# Controllers.net
KiCad netlist of a schematic drawn in Altium Designer
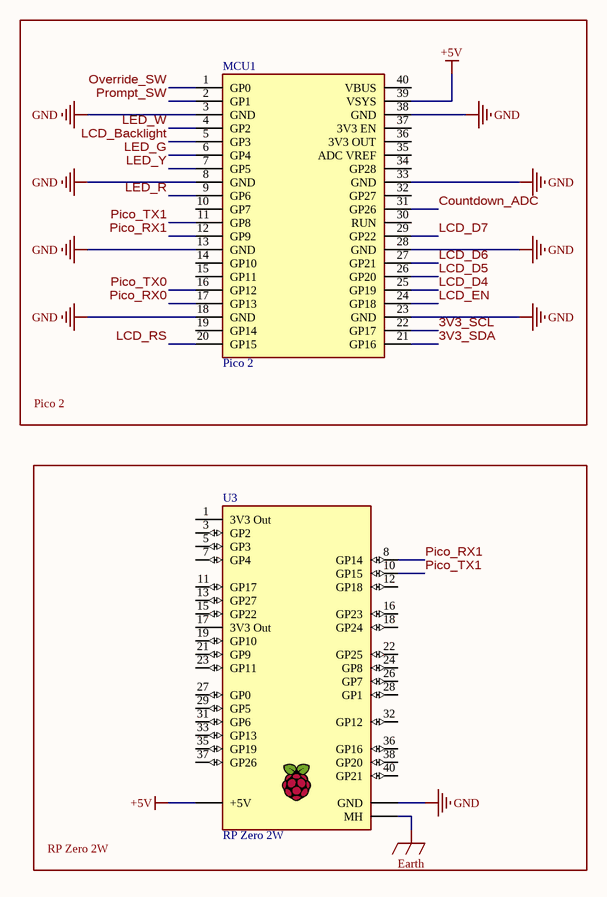
[diagram p0: Controllers.SchDoc]

(export (version "E")
  (design (tool "Eeschema 10.0.6"))
  (components
    (comp (ref "MCU1")
      (value "Pico 2")
      (footprint "[Pi] Pico 2")
      (description "SC1631")
      (libsource (lib "Devices") (part "[Pi] Pico 2"))
    )
    (comp (ref "U3")
      (value "RP Zero 2W")
      (footprint "[Pi] Zero 2W")
      (libsource (lib "Devices") (part "[Pi] Zero 2W"))
    )
  )
  (nets
    (net (code "1") (name "+5V") (class "Default")
      (node (ref "MCU1") (pin "39") (pinfunction "VSYS_39") (pintype "passive"))
      (node (ref "U3") (pin "+5V") (pinfunction "+5V_+5V") (pintype "power_in"))
    )
    (net (code "2") (name "/3V3_SCL") (class "Default")
      (node (ref "MCU1") (pin "22") (pinfunction "GP17_22") (pintype "passive"))
    )
    (net (code "3") (name "/3V3_SDA") (class "Default")
      (node (ref "MCU1") (pin "21") (pinfunction "GP16_21") (pintype "passive"))
    )
    (net (code "4") (name "/Countdown_ADC") (class "Default")
      (node (ref "MCU1") (pin "31") (pinfunction "GP26_31") (pintype "passive"))
    )
    (net (code "5") (name "/LCD_Backlight") (class "Default")
      (node (ref "MCU1") (pin "5") (pinfunction "GP3_5") (pintype "passive"))
    )
    (net (code "6") (name "/LCD_D4") (class "Default")
      (node (ref "MCU1") (pin "25") (pinfunction "GP19_25") (pintype "passive"))
    )
    (net (code "7") (name "/LCD_D5") (class "Default")
      (node (ref "MCU1") (pin "26") (pinfunction "GP20_26") (pintype "passive"))
    )
    (net (code "8") (name "/LCD_D6") (class "Default")
      (node (ref "MCU1") (pin "27") (pinfunction "GP21_27") (pintype "passive"))
    )
    (net (code "9") (name "/LCD_D7") (class "Default")
      (node (ref "MCU1") (pin "29") (pinfunction "GP22_29") (pintype "passive"))
    )
    (net (code "10") (name "/LCD_EN") (class "Default")
      (node (ref "MCU1") (pin "24") (pinfunction "GP18_24") (pintype "passive"))
    )
    (net (code "11") (name "/LCD_RS") (class "Default")
      (node (ref "MCU1") (pin "20") (pinfunction "GP15_20") (pintype "passive"))
    )
    (net (code "12") (name "/LED_G") (class "Default")
      (node (ref "MCU1") (pin "6") (pinfunction "GP4_6") (pintype "passive"))
    )
    (net (code "13") (name "/LED_R") (class "Default")
      (node (ref "MCU1") (pin "9") (pinfunction "GP6_9") (pintype "passive"))
    )
    (net (code "14") (name "/LED_W") (class "Default")
      (node (ref "MCU1") (pin "4") (pinfunction "GP2_4") (pintype "passive"))
    )
    (net (code "15") (name "/LED_Y") (class "Default")
      (node (ref "MCU1") (pin "7") (pinfunction "GP5_7") (pintype "passive"))
    )
    (net (code "16") (name "/Override_SW") (class "Default")
      (node (ref "MCU1") (pin "1") (pinfunction "GP0_1") (pintype "passive"))
    )
    (net (code "17") (name "/Pico_RX0") (class "Default")
      (node (ref "MCU1") (pin "17") (pinfunction "GP13_17") (pintype "passive"))
    )
    (net (code "18") (name "/Pico_RX1") (class "Default")
      (node (ref "MCU1") (pin "12") (pinfunction "GP9_12") (pintype "passive"))
      (node (ref "U3") (pin "8") (pinfunction "GP14_8") (pintype "bidirectional"))
    )
    (net (code "19") (name "/Pico_TX0") (class "Default")
      (node (ref "MCU1") (pin "16") (pinfunction "GP12_16") (pintype "passive"))
    )
    (net (code "20") (name "/Pico_TX1") (class "Default")
      (node (ref "MCU1") (pin "11") (pinfunction "GP8_11") (pintype "passive"))
      (node (ref "U3") (pin "10") (pinfunction "GP15_10") (pintype "bidirectional"))
    )
    (net (code "21") (name "/Prompt_SW") (class "Default")
      (node (ref "MCU1") (pin "2") (pinfunction "GP1_2") (pintype "passive"))
    )
    (net (code "22") (name "Earth") (class "Default")
      (node (ref "U3") (pin "MH") (pinfunction "MH_MH") (pintype "power_in"))
    )
    (net (code "23") (name "GND") (class "Default")
      (node (ref "MCU1") (pin "13") (pinfunction "GND_13") (pintype "passive"))
      (node (ref "MCU1") (pin "18") (pinfunction "GND_18") (pintype "passive"))
      (node (ref "MCU1") (pin "23") (pinfunction "GND_23") (pintype "passive"))
      (node (ref "MCU1") (pin "28") (pinfunction "GND_28") (pintype "passive"))
      (node (ref "MCU1") (pin "3") (pinfunction "GND_3") (pintype "passive"))
      (node (ref "MCU1") (pin "33") (pinfunction "GND_33") (pintype "passive"))
      (node (ref "MCU1") (pin "38") (pinfunction "GND_38") (pintype "passive"))
      (node (ref "MCU1") (pin "8") (pinfunction "GND_8") (pintype "passive"))
      (node (ref "U3") (pin "GND") (pinfunction "GND_GND") (pintype "power_in"))
    )
    (net (code "24") (name "unconnected-(MCU1-3V3_EN-Pad37)") (class "Default")
      (node (ref "MCU1") (pin "37") (pinfunction "3V3_EN_37") (pintype "passive"))
    )
    (net (code "25") (name "unconnected-(MCU1-3V3_OUT-Pad36)") (class "Default")
      (node (ref "MCU1") (pin "36") (pinfunction "3V3_OUT_36") (pintype "passive"))
    )
    (net (code "26") (name "unconnected-(MCU1-ADC_VREF-Pad35)") (class "Default")
      (node (ref "MCU1") (pin "35") (pinfunction "ADC_VREF_35") (pintype "passive"))
    )
    (net (code "27") (name "unconnected-(MCU1-GP7-Pad10)") (class "Default")
      (node (ref "MCU1") (pin "10") (pinfunction "GP7_10") (pintype "passive"))
    )
    (net (code "28") (name "unconnected-(MCU1-GP10-Pad14)") (class "Default")
      (node (ref "MCU1") (pin "14") (pinfunction "GP10_14") (pintype "passive"))
    )
    (net (code "29") (name "unconnected-(MCU1-GP11-Pad15)") (class "Default")
      (node (ref "MCU1") (pin "15") (pinfunction "GP11_15") (pintype "passive"))
    )
    (net (code "30") (name "unconnected-(MCU1-GP14-Pad19)") (class "Default")
      (node (ref "MCU1") (pin "19") (pinfunction "GP14_19") (pintype "passive"))
    )
    (net (code "31") (name "unconnected-(MCU1-GP27-Pad32)") (class "Default")
      (node (ref "MCU1") (pin "32") (pinfunction "GP27_32") (pintype "passive"))
    )
    (net (code "32") (name "unconnected-(MCU1-GP28-Pad34)") (class "Default")
      (node (ref "MCU1") (pin "34") (pinfunction "GP28_34") (pintype "passive"))
    )
    (net (code "33") (name "unconnected-(MCU1-RUN-Pad30)") (class "Default")
      (node (ref "MCU1") (pin "30") (pinfunction "RUN_30") (pintype "passive"))
    )
    (net (code "34") (name "unconnected-(MCU1-VBUS-Pad40)") (class "Default")
      (node (ref "MCU1") (pin "40") (pinfunction "VBUS_40") (pintype "passive"))
    )
    (net (code "35") (name "unconnected-(U3-3V3_Out-Pad1)") (class "Default")
      (node (ref "U3") (pin "1") (pinfunction "3V3_Out_1") (pintype "power_in"))
    )
    (net (code "36") (name "unconnected-(U3-3V3_Out-Pad17)") (class "Default")
      (node (ref "U3") (pin "17") (pinfunction "3V3_Out_17") (pintype "power_in"))
    )
    (net (code "37") (name "unconnected-(U3-GP0-Pad27)") (class "Default")
      (node (ref "U3") (pin "27") (pinfunction "GP0_27") (pintype "bidirectional"))
    )
    (net (code "38") (name "unconnected-(U3-GP1-Pad28)") (class "Default")
      (node (ref "U3") (pin "28") (pinfunction "GP1_28") (pintype "bidirectional"))
    )
    (net (code "39") (name "unconnected-(U3-GP2-Pad3)") (class "Default")
      (node (ref "U3") (pin "3") (pinfunction "GP2_3") (pintype "bidirectional"))
    )
    (net (code "40") (name "unconnected-(U3-GP3-Pad5)") (class "Default")
      (node (ref "U3") (pin "5") (pinfunction "GP3_5") (pintype "bidirectional"))
    )
    (net (code "41") (name "unconnected-(U3-GP4-Pad7)") (class "Default")
      (node (ref "U3") (pin "7") (pinfunction "GP4_7") (pintype "bidirectional"))
    )
    (net (code "42") (name "unconnected-(U3-GP5-Pad29)") (class "Default")
      (node (ref "U3") (pin "29") (pinfunction "GP5_29") (pintype "bidirectional"))
    )
    (net (code "43") (name "unconnected-(U3-GP6-Pad31)") (class "Default")
      (node (ref "U3") (pin "31") (pinfunction "GP6_31") (pintype "bidirectional"))
    )
    (net (code "44") (name "unconnected-(U3-GP7-Pad26)") (class "Default")
      (node (ref "U3") (pin "26") (pinfunction "GP7_26") (pintype "bidirectional"))
    )
    (net (code "45") (name "unconnected-(U3-GP8-Pad24)") (class "Default")
      (node (ref "U3") (pin "24") (pinfunction "GP8_24") (pintype "bidirectional"))
    )
    (net (code "46") (name "unconnected-(U3-GP9-Pad21)") (class "Default")
      (node (ref "U3") (pin "21") (pinfunction "GP9_21") (pintype "bidirectional"))
    )
    (net (code "47") (name "unconnected-(U3-GP10-Pad19)") (class "Default")
      (node (ref "U3") (pin "19") (pinfunction "GP10_19") (pintype "bidirectional"))
    )
    (net (code "48") (name "unconnected-(U3-GP11-Pad23)") (class "Default")
      (node (ref "U3") (pin "23") (pinfunction "GP11_23") (pintype "bidirectional"))
    )
    (net (code "49") (name "unconnected-(U3-GP12-Pad32)") (class "Default")
      (node (ref "U3") (pin "32") (pinfunction "GP12_32") (pintype "bidirectional"))
    )
    (net (code "50") (name "unconnected-(U3-GP13-Pad33)") (class "Default")
      (node (ref "U3") (pin "33") (pinfunction "GP13_33") (pintype "bidirectional"))
    )
    (net (code "51") (name "unconnected-(U3-GP16-Pad36)") (class "Default")
      (node (ref "U3") (pin "36") (pinfunction "GP16_36") (pintype "bidirectional"))
    )
    (net (code "52") (name "unconnected-(U3-GP17-Pad11)") (class "Default")
      (node (ref "U3") (pin "11") (pinfunction "GP17_11") (pintype "bidirectional"))
    )
    (net (code "53") (name "unconnected-(U3-GP18-Pad12)") (class "Default")
      (node (ref "U3") (pin "12") (pinfunction "GP18_12") (pintype "bidirectional"))
    )
    (net (code "54") (name "unconnected-(U3-GP19-Pad35)") (class "Default")
      (node (ref "U3") (pin "35") (pinfunction "GP19_35") (pintype "bidirectional"))
    )
    (net (code "55") (name "unconnected-(U3-GP20-Pad38)") (class "Default")
      (node (ref "U3") (pin "38") (pinfunction "GP20_38") (pintype "bidirectional"))
    )
    (net (code "56") (name "unconnected-(U3-GP21-Pad40)") (class "Default")
      (node (ref "U3") (pin "40") (pinfunction "GP21_40") (pintype "bidirectional"))
    )
    (net (code "57") (name "unconnected-(U3-GP22-Pad15)") (class "Default")
      (node (ref "U3") (pin "15") (pinfunction "GP22_15") (pintype "bidirectional"))
    )
    (net (code "58") (name "unconnected-(U3-GP23-Pad16)") (class "Default")
      (node (ref "U3") (pin "16") (pinfunction "GP23_16") (pintype "bidirectional"))
    )
    (net (code "59") (name "unconnected-(U3-GP24-Pad18)") (class "Default")
      (node (ref "U3") (pin "18") (pinfunction "GP24_18") (pintype "bidirectional"))
    )
    (net (code "60") (name "unconnected-(U3-GP25-Pad22)") (class "Default")
      (node (ref "U3") (pin "22") (pinfunction "GP25_22") (pintype "bidirectional"))
    )
    (net (code "61") (name "unconnected-(U3-GP26-Pad37)") (class "Default")
      (node (ref "U3") (pin "37") (pinfunction "GP26_37") (pintype "bidirectional"))
    )
    (net (code "62") (name "unconnected-(U3-GP27-Pad13)") (class "Default")
      (node (ref "U3") (pin "13") (pinfunction "GP27_13") (pintype "bidirectional"))
    )
  )
)
